# rel-reset.net
KiCad netlist of a schematic drawn in EAGLE
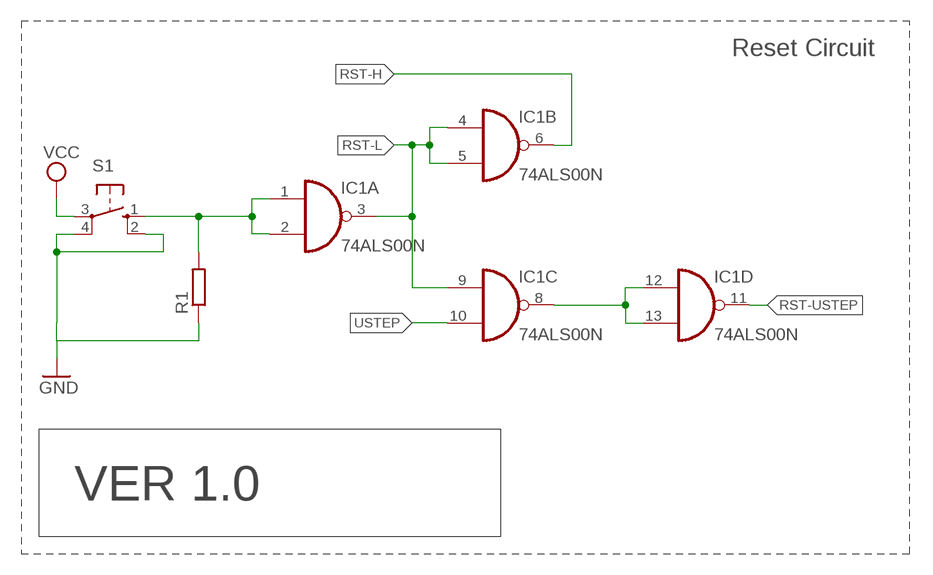
[diagram p0: schematic, sheet 1]

(export (version "E")
  (design (tool "Eeschema 10.0.6"))
  (components
    (comp (ref "IC1")
      (value "74ALS00N")
      (footprint "eagle-import:DIL14")
      (libsource (lib "eagle-import") (part "7400NALS"))
    )
    (comp (ref "R1")
      (value "R-EU_0204/5")
      (footprint "eagle-import:0204_5")
      (libsource (lib "eagle-import") (part "R-EU_0204/5"))
    )
    (comp (ref "S1")
      (value "10-XX")
      (footprint "eagle-import:B3F-10XX")
      (fields (field (name "MPN") "B3F-1000"))
      (libsource (lib "eagle-import") (part "10-XX"))
    )
  )
  (nets
    (net (code "1") (name "GND") (class "Default")
      (node (ref "R1") (pin "1") (pinfunction "1_1") (pintype "passive"))
      (node (ref "S1") (pin "2") (pinfunction "S1_2") (pintype "passive"))
      (node (ref "S1") (pin "4") (pinfunction "P1_4") (pintype "passive"))
    )
    (net (code "2") (name "Net-(IC1A-I0)") (class "Default")
      (node (ref "IC1") (pin "1") (pinfunction "I0_1") (pintype "input"))
      (node (ref "IC1") (pin "2") (pinfunction "I1_2") (pintype "input"))
      (node (ref "R1") (pin "2") (pinfunction "2_2") (pintype "passive"))
      (node (ref "S1") (pin "1") (pinfunction "S_1") (pintype "passive"))
    )
    (net (code "3") (name "Net-(IC1C-O)") (class "Default")
      (node (ref "IC1") (pin "12") (pinfunction "I0_12") (pintype "input"))
      (node (ref "IC1") (pin "13") (pinfunction "I1_13") (pintype "input"))
      (node (ref "IC1") (pin "8") (pinfunction "O_8") (pintype "output"))
    )
    (net (code "4") (name "RST-H") (class "Default")
      (node (ref "IC1") (pin "6") (pinfunction "O_6") (pintype "output"))
    )
    (net (code "5") (name "RST-L") (class "Default")
      (node (ref "IC1") (pin "3") (pinfunction "O_3") (pintype "output"))
      (node (ref "IC1") (pin "4") (pinfunction "I0_4") (pintype "input"))
      (node (ref "IC1") (pin "5") (pinfunction "I1_5") (pintype "input"))
      (node (ref "IC1") (pin "9") (pinfunction "I0_9") (pintype "input"))
    )
    (net (code "6") (name "RST-USTEP") (class "Default")
      (node (ref "IC1") (pin "11") (pinfunction "O_11") (pintype "output"))
    )
    (net (code "7") (name "USTEP") (class "Default")
      (node (ref "IC1") (pin "10") (pinfunction "I1_10") (pintype "input"))
    )
    (net (code "8") (name "VCC") (class "Default")
      (node (ref "S1") (pin "3") (pinfunction "P_3") (pintype "passive"))
    )
  )
)
